# Lab_7_-_Schematic.net
KiCad netlist of a schematic drawn in EAGLE
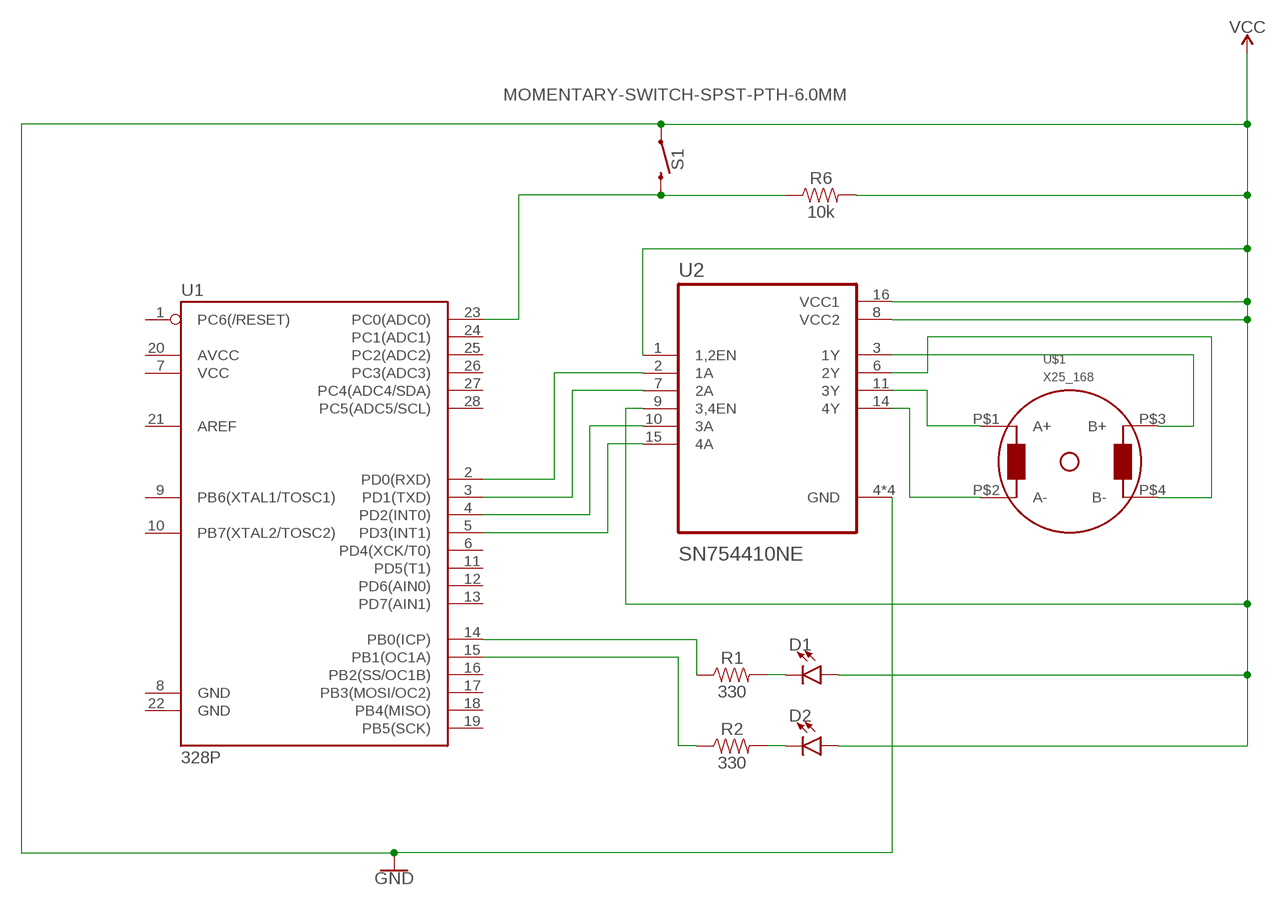
[diagram p0: schematic, sheet 1]

(export (version "E")
  (design (tool "Eeschema 10.0.6"))
  (components
    (comp (ref "D1")
      (value "LED-3MM-NO_SILK")
      (footprint "eagle-import:LED_3MM-NS")
      (libsource (lib "eagle-import") (part "LED-3MM-NO_SILK"))
    )
    (comp (ref "D2")
      (value "LED-3MM-NO_SILK")
      (footprint "eagle-import:LED_3MM-NS")
      (libsource (lib "eagle-import") (part "LED-3MM-NO_SILK"))
    )
    (comp (ref "R1")
      (value "330")
      (footprint "eagle-import:AXIAL-0.3")
      (libsource (lib "eagle-import") (part "330OHM-HORIZ-1/10W-5%"))
    )
    (comp (ref "R2")
      (value "330")
      (footprint "eagle-import:AXIAL-0.3")
      (libsource (lib "eagle-import") (part "330OHM-HORIZ-1/10W-5%"))
    )
    (comp (ref "R6")
      (value "10k")
      (footprint "eagle-import:AXIAL-0.3")
      (libsource (lib "eagle-import") (part "10KOHM-HORIZ-1/4W-1%"))
    )
    (comp (ref "S1")
      (value "MOMENTARY-SWITCH-SPST-PTH-6.0MM")
      (footprint "eagle-import:TACTILE_SWITCH_PTH_6.0MM")
      (libsource (lib "eagle-import") (part "MOMENTARY-SWITCH-SPST-PTH-6.0MM"))
    )
    (comp (ref "U$1")
      (value "X25_168")
      (footprint "eagle-import:X25_168")
      (libsource (lib "eagle-import") (part "X25_168"))
    )
    (comp (ref "U1")
      (value "328P")
      (footprint "eagle-import:DIP28")
      (libsource (lib "eagle-import") (part "ATMEGA328P_PDIP"))
    )
    (comp (ref "U2")
      (value "SN754410NE")
      (footprint "eagle-import:DIP762W45P254L1980H508Q16")
      (fields (field (name "MF") "Texas Instruments"))
      (libsource (lib "eagle-import") (part "SN754410NE"))
    )
  )
  (nets
    (net (code "1") (name "GND") (class "Default")
      (node (ref "D1") (pin "A") (pinfunction "A_A") (pintype "passive"))
      (node (ref "D2") (pin "A") (pinfunction "A_A") (pintype "passive"))
      (node (ref "R6") (pin "P$2") (pinfunction "2_P$2") (pintype "passive"))
      (node (ref "S1") (pin "1") (pinfunction "1_1") (pintype "passive"))
      (node (ref "U2") (pin "1") (pinfunction "1,2EN_1") (pintype "input"))
      (node (ref "U2") (pin "12") (pinfunction "GND_12") (pintype "power_in"))
      (node (ref "U2") (pin "13") (pinfunction "GND_13") (pintype "power_in"))
      (node (ref "U2") (pin "16") (pinfunction "VCC1_16") (pintype "power_in"))
      (node (ref "U2") (pin "4") (pinfunction "GND_4") (pintype "power_in"))
      (node (ref "U2") (pin "5") (pinfunction "GND_5") (pintype "power_in"))
      (node (ref "U2") (pin "8") (pinfunction "VCC2_8") (pintype "power_in"))
      (node (ref "U2") (pin "9") (pinfunction "3,4EN_9") (pintype "input"))
    )
    (net (code "2") (name "Net-(D1-C)") (class "Default")
      (node (ref "D1") (pin "K") (pinfunction "C_K") (pintype "passive"))
      (node (ref "R1") (pin "P$2") (pinfunction "2_P$2") (pintype "passive"))
    )
    (net (code "3") (name "Net-(D2-C)") (class "Default")
      (node (ref "D2") (pin "K") (pinfunction "C_K") (pintype "passive"))
      (node (ref "R2") (pin "P$2") (pinfunction "2_P$2") (pintype "passive"))
    )
    (net (code "4") (name "Net-(R1-1)") (class "Default")
      (node (ref "R1") (pin "P$1") (pinfunction "1_P$1") (pintype "passive"))
      (node (ref "U1") (pin "14") (pinfunction "PB0(ICP)_14") (pintype "bidirectional"))
    )
    (net (code "5") (name "Net-(R2-1)") (class "Default")
      (node (ref "R2") (pin "P$1") (pinfunction "1_P$1") (pintype "passive"))
      (node (ref "U1") (pin "15") (pinfunction "PB1(OC1A)_15") (pintype "bidirectional"))
    )
    (net (code "6") (name "Net-(R6-1)") (class "Default")
      (node (ref "R6") (pin "P$1") (pinfunction "1_P$1") (pintype "passive"))
      (node (ref "S1") (pin "3") (pinfunction "2_3") (pintype "passive"))
      (node (ref "U1") (pin "23") (pinfunction "PC0(ADC0)_23") (pintype "bidirectional"))
    )
    (net (code "7") (name "Net-(U$1-A+)") (class "Default")
      (node (ref "U$1") (pin "P$1") (pinfunction "A+_P$1") (pintype "input"))
      (node (ref "U2") (pin "11") (pinfunction "3Y_11") (pintype "output"))
    )
    (net (code "8") (name "Net-(U$1-A-)") (class "Default")
      (node (ref "U$1") (pin "P$2") (pinfunction "A-_P$2") (pintype "input"))
      (node (ref "U2") (pin "14") (pinfunction "4Y_14") (pintype "output"))
    )
    (net (code "9") (name "Net-(U$1-B+)") (class "Default")
      (node (ref "U$1") (pin "P$3") (pinfunction "B+_P$3") (pintype "input"))
      (node (ref "U2") (pin "3") (pinfunction "1Y_3") (pintype "output"))
    )
    (net (code "10") (name "Net-(U$1-B-)") (class "Default")
      (node (ref "U$1") (pin "P$4") (pinfunction "B-_P$4") (pintype "input"))
      (node (ref "U2") (pin "6") (pinfunction "2Y_6") (pintype "output"))
    )
    (net (code "11") (name "Net-(U1-PD0(RXD))") (class "Default")
      (node (ref "U1") (pin "2") (pinfunction "PD0(RXD)_2") (pintype "bidirectional"))
      (node (ref "U2") (pin "2") (pinfunction "1A_2") (pintype "input"))
    )
    (net (code "12") (name "Net-(U1-PD1(TXD))") (class "Default")
      (node (ref "U1") (pin "3") (pinfunction "PD1(TXD)_3") (pintype "bidirectional"))
      (node (ref "U2") (pin "7") (pinfunction "2A_7") (pintype "input"))
    )
    (net (code "13") (name "Net-(U1-PD2(INT0))") (class "Default")
      (node (ref "U1") (pin "4") (pinfunction "PD2(INT0)_4") (pintype "bidirectional"))
      (node (ref "U2") (pin "10") (pinfunction "3A_10") (pintype "input"))
    )
    (net (code "14") (name "Net-(U1-PD3(INT1))") (class "Default")
      (node (ref "U1") (pin "5") (pinfunction "PD3(INT1)_5") (pintype "bidirectional"))
      (node (ref "U2") (pin "15") (pinfunction "4A_15") (pintype "input"))
    )
    (net (code "15") (name "unconnected-(U1-AREF-Pad21)") (class "Default")
      (node (ref "U1") (pin "21") (pinfunction "AREF_21") (pintype "bidirectional"))
    )
    (net (code "16") (name "unconnected-(U1-AVCC-Pad20)") (class "Default")
      (node (ref "U1") (pin "20") (pinfunction "AVCC_20") (pintype "bidirectional"))
    )
    (net (code "17") (name "unconnected-(U1-GND-Pad8)") (class "Default")
      (node (ref "U1") (pin "8") (pinfunction "GND_8") (pintype "bidirectional"))
    )
    (net (code "18") (name "unconnected-(U1-GND-Pad22)") (class "Default")
      (node (ref "U1") (pin "22") (pinfunction "GND_22") (pintype "bidirectional"))
    )
    (net (code "19") (name "unconnected-(U1-PB2(SS{slash}OC1B)-Pad16)") (class "Default")
      (node (ref "U1") (pin "16") (pinfunction "PB2(SS/OC1B)_16") (pintype "bidirectional"))
    )
    (net (code "20") (name "unconnected-(U1-PB3(MOSI{slash}OC2)-Pad17)") (class "Default")
      (node (ref "U1") (pin "17") (pinfunction "PB3(MOSI/OC2)_17") (pintype "bidirectional"))
    )
    (net (code "21") (name "unconnected-(U1-PB4(MISO)-Pad18)") (class "Default")
      (node (ref "U1") (pin "18") (pinfunction "PB4(MISO)_18") (pintype "bidirectional"))
    )
    (net (code "22") (name "unconnected-(U1-PB5(SCK)-Pad19)") (class "Default")
      (node (ref "U1") (pin "19") (pinfunction "PB5(SCK)_19") (pintype "bidirectional"))
    )
    (net (code "23") (name "unconnected-(U1-PB6(XTAL1{slash}TOSC1)-Pad9)") (class "Default")
      (node (ref "U1") (pin "9") (pinfunction "PB6(XTAL1/TOSC1)_9") (pintype "bidirectional"))
    )
    (net (code "24") (name "unconnected-(U1-PB7(XTAL2{slash}TOSC2)-Pad10)") (class "Default")
      (node (ref "U1") (pin "10") (pinfunction "PB7(XTAL2/TOSC2)_10") (pintype "bidirectional"))
    )
    (net (code "25") (name "unconnected-(U1-PC1(ADC1)-Pad24)") (class "Default")
      (node (ref "U1") (pin "24") (pinfunction "PC1(ADC1)_24") (pintype "bidirectional"))
    )
    (net (code "26") (name "unconnected-(U1-PC2(ADC2)-Pad25)") (class "Default")
      (node (ref "U1") (pin "25") (pinfunction "PC2(ADC2)_25") (pintype "bidirectional"))
    )
    (net (code "27") (name "unconnected-(U1-PC3(ADC3)-Pad26)") (class "Default")
      (node (ref "U1") (pin "26") (pinfunction "PC3(ADC3)_26") (pintype "bidirectional"))
    )
    (net (code "28") (name "unconnected-(U1-PC4(ADC4{slash}SDA)-Pad27)") (class "Default")
      (node (ref "U1") (pin "27") (pinfunction "PC4(ADC4/SDA)_27") (pintype "bidirectional"))
    )
    (net (code "29") (name "unconnected-(U1-PC5(ADC5{slash}SCL)-Pad28)") (class "Default")
      (node (ref "U1") (pin "28") (pinfunction "PC5(ADC5/SCL)_28") (pintype "bidirectional"))
    )
    (net (code "30") (name "unconnected-(U1-PC6({slash}RESET)-Pad1)") (class "Default")
      (node (ref "U1") (pin "1") (pinfunction "PC6(/RESET)_1") (pintype "bidirectional"))
    )
    (net (code "31") (name "unconnected-(U1-PD4(XCK{slash}T0)-Pad6)") (class "Default")
      (node (ref "U1") (pin "6") (pinfunction "PD4(XCK/T0)_6") (pintype "bidirectional"))
    )
    (net (code "32") (name "unconnected-(U1-PD5(T1)-Pad11)") (class "Default")
      (node (ref "U1") (pin "11") (pinfunction "PD5(T1)_11") (pintype "bidirectional"))
    )
    (net (code "33") (name "unconnected-(U1-PD6(AIN0)-Pad12)") (class "Default")
      (node (ref "U1") (pin "12") (pinfunction "PD6(AIN0)_12") (pintype "bidirectional"))
    )
    (net (code "34") (name "unconnected-(U1-PD7(AIN1)-Pad13)") (class "Default")
      (node (ref "U1") (pin "13") (pinfunction "PD7(AIN1)_13") (pintype "bidirectional"))
    )
    (net (code "35") (name "unconnected-(U1-VCC-Pad7)") (class "Default")
      (node (ref "U1") (pin "7") (pinfunction "VCC_7") (pintype "bidirectional"))
    )
  )
)
